# clock_sync.net
KiCad netlist of a schematic drawn in EAGLE
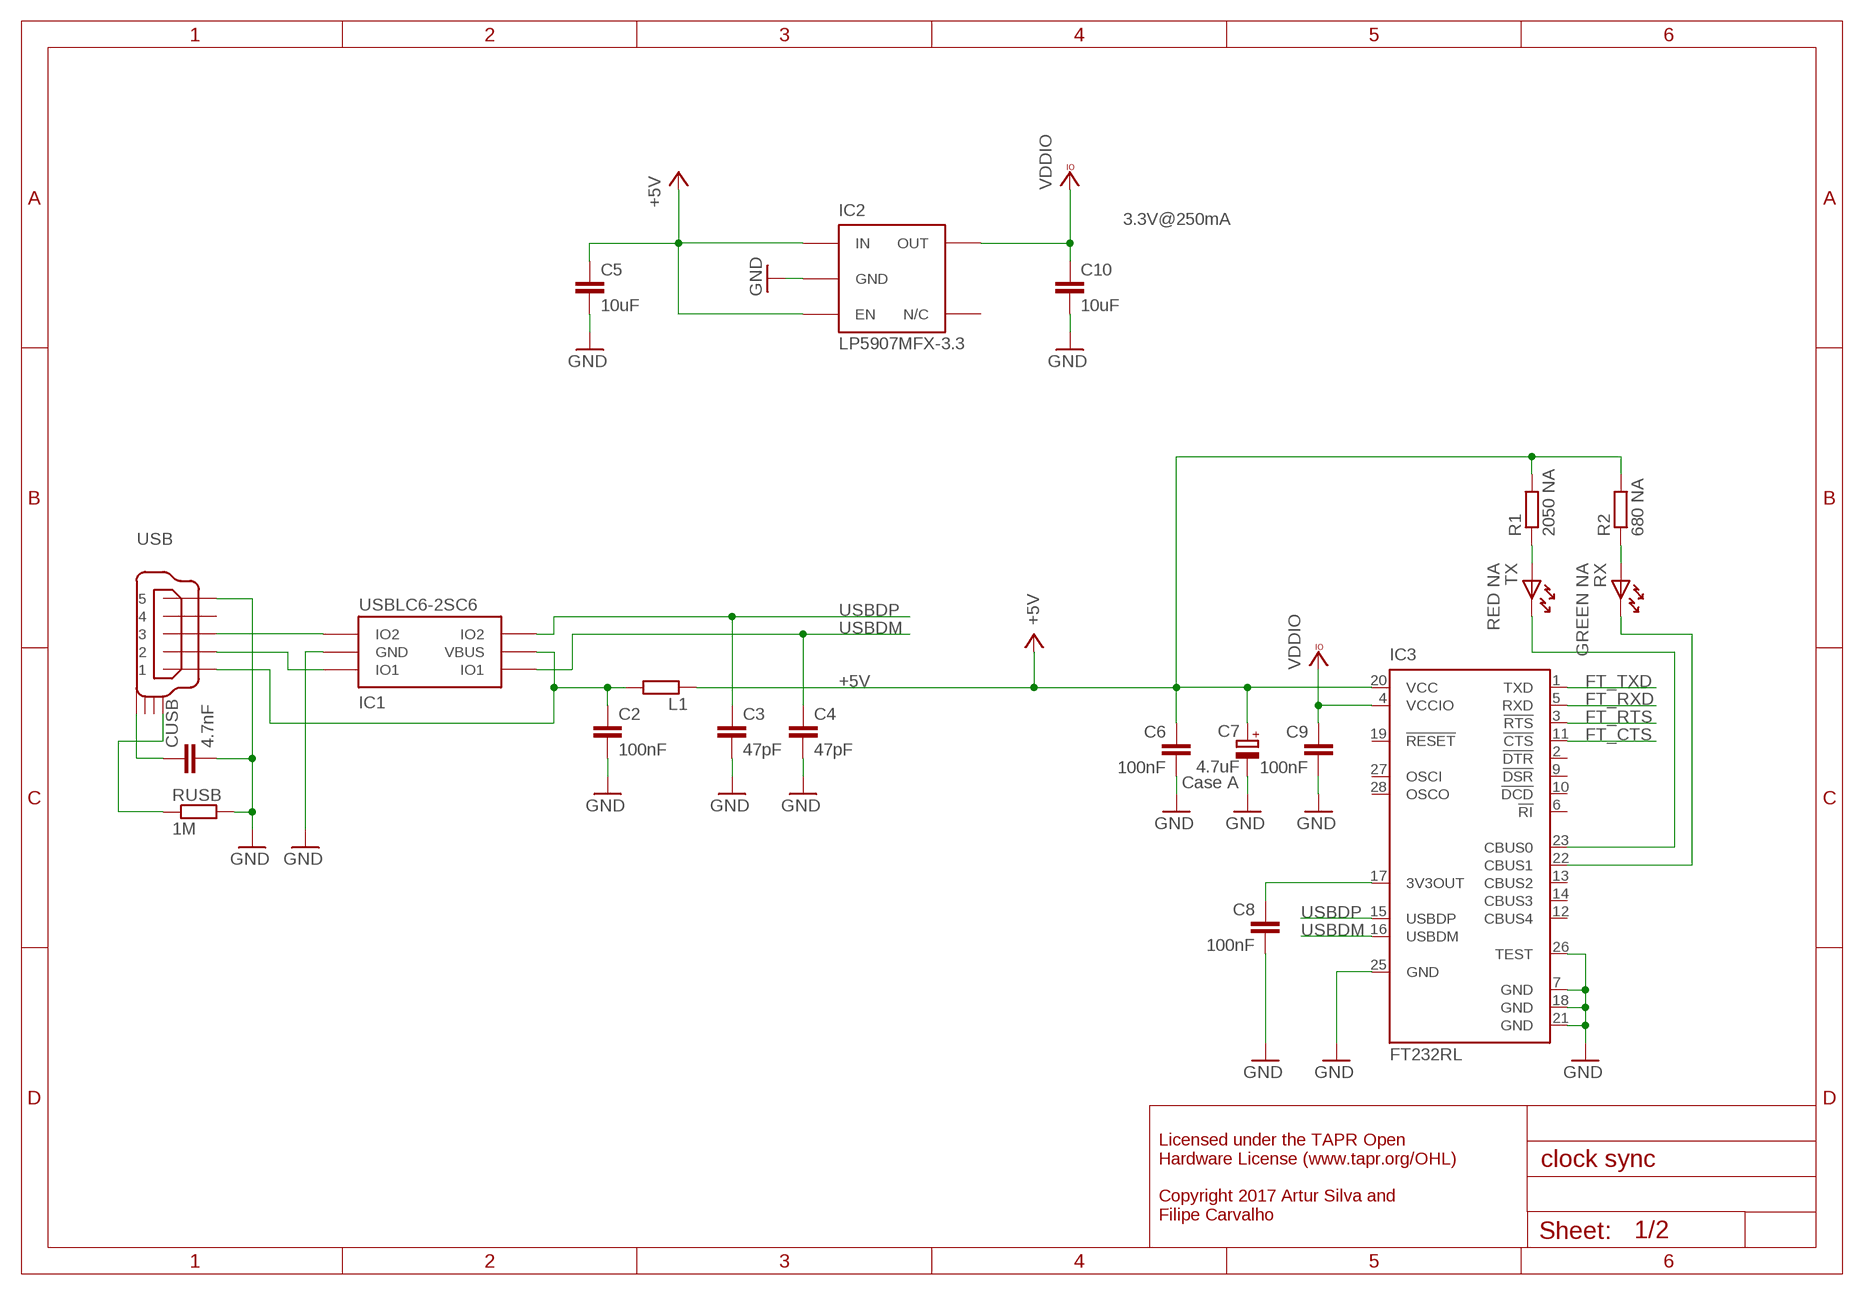
[diagram p0: schematic, sheet 1]
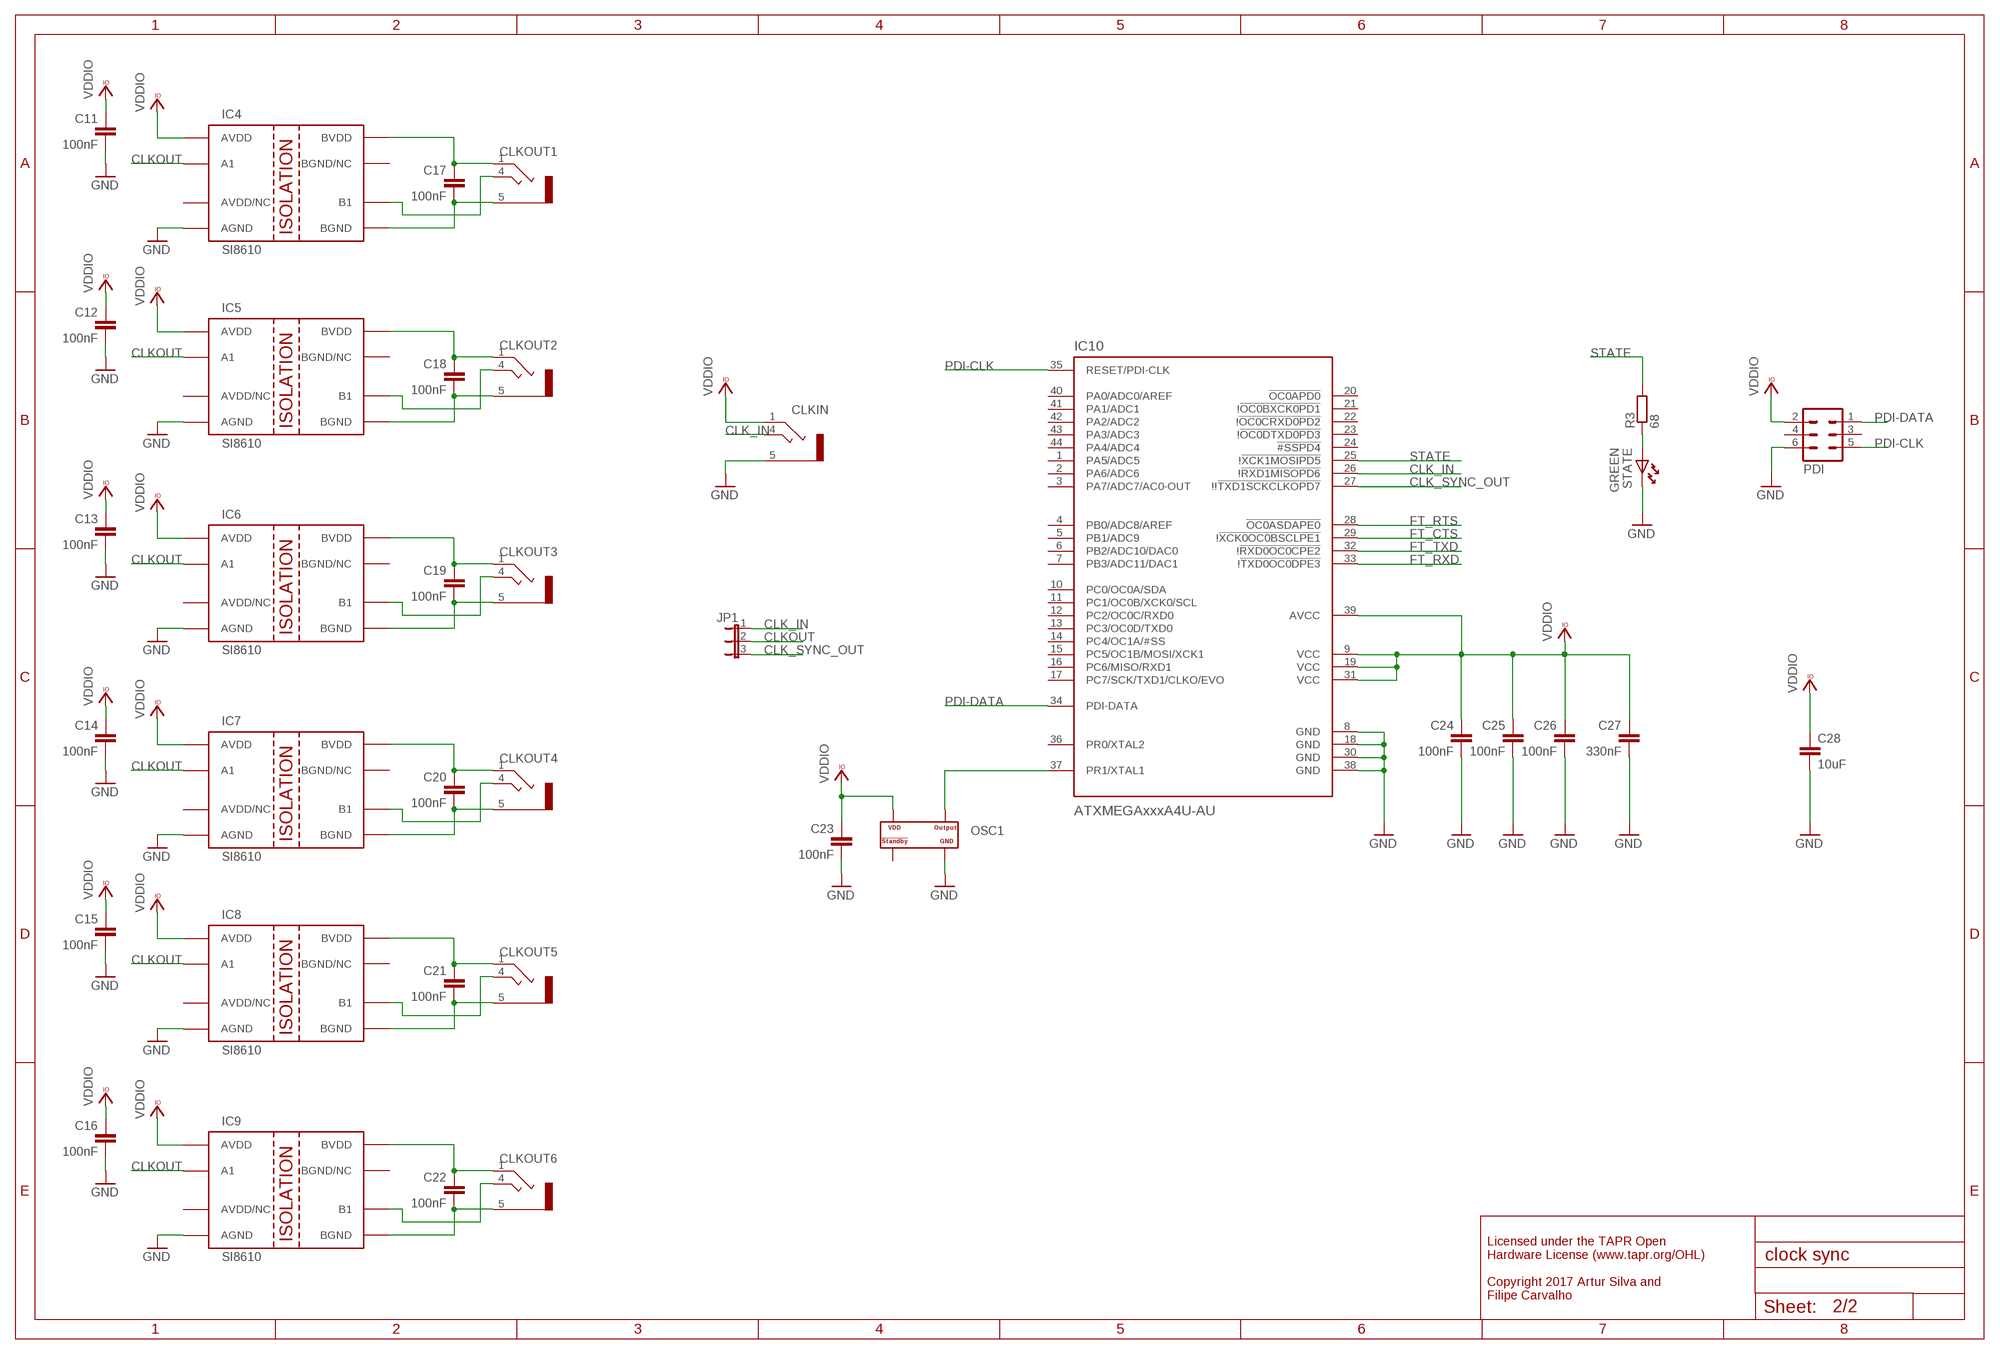
[diagram p1: schematic, sheet 2]

(export (version "E")
  (design (tool "Eeschema 10.0.6"))
  (components
    (comp (ref "C11")
      (value "100nF")
      (footprint "eagle-import:C0402")
      (libsource (lib "eagle-import") (part "C-EUC0402"))
    )
    (comp (ref "C12")
      (value "100nF")
      (footprint "eagle-import:C0402")
      (libsource (lib "eagle-import") (part "C-EUC0402"))
    )
    (comp (ref "C13")
      (value "100nF")
      (footprint "eagle-import:C0402")
      (libsource (lib "eagle-import") (part "C-EUC0402"))
    )
    (comp (ref "C14")
      (value "100nF")
      (footprint "eagle-import:C0402")
      (libsource (lib "eagle-import") (part "C-EUC0402"))
    )
    (comp (ref "C15")
      (value "100nF")
      (footprint "eagle-import:C0402")
      (libsource (lib "eagle-import") (part "C-EUC0402"))
    )
    (comp (ref "C16")
      (value "100nF")
      (footprint "eagle-import:C0402")
      (libsource (lib "eagle-import") (part "C-EUC0402"))
    )
    (comp (ref "C17")
      (value "100nF")
      (footprint "eagle-import:C0402")
      (libsource (lib "eagle-import") (part "C-EUC0402"))
    )
    (comp (ref "C18")
      (value "100nF")
      (footprint "eagle-import:C0402")
      (libsource (lib "eagle-import") (part "C-EUC0402"))
    )
    (comp (ref "C19")
      (value "100nF")
      (footprint "eagle-import:C0402")
      (libsource (lib "eagle-import") (part "C-EUC0402"))
    )
    (comp (ref "C20")
      (value "100nF")
      (footprint "eagle-import:C0402")
      (libsource (lib "eagle-import") (part "C-EUC0402"))
    )
    (comp (ref "C21")
      (value "100nF")
      (footprint "eagle-import:C0402")
      (libsource (lib "eagle-import") (part "C-EUC0402"))
    )
    (comp (ref "C22")
      (value "100nF")
      (footprint "eagle-import:C0402")
      (libsource (lib "eagle-import") (part "C-EUC0402"))
    )
    (comp (ref "C23")
      (value "100nF")
      (footprint "eagle-import:C0402")
      (libsource (lib "eagle-import") (part "C-EUC0402"))
    )
    (comp (ref "C24")
      (value "100nF")
      (footprint "eagle-import:C0402")
      (libsource (lib "eagle-import") (part "C-EUC0402"))
    )
    (comp (ref "C25")
      (value "100nF")
      (footprint "eagle-import:C0402")
      (libsource (lib "eagle-import") (part "C-EUC0402"))
    )
    (comp (ref "C26")
      (value "100nF")
      (footprint "eagle-import:C0402")
      (libsource (lib "eagle-import") (part "C-EUC0402"))
    )
    (comp (ref "C27")
      (value "330nF")
      (footprint "eagle-import:C0402")
      (libsource (lib "eagle-import") (part "C-EUC0402"))
    )
    (comp (ref "C28")
      (value "10uF")
      (footprint "eagle-import:C0603")
      (libsource (lib "eagle-import") (part "C-EUC0603"))
    )
    (comp (ref "CLKIN")
      (value "STEREO_JACK")
      (footprint "eagle-import:35RASMT2BHNTRX")
      (libsource (lib "eagle-import") (part "STEREO_JACK"))
    )
    (comp (ref "CLKOUT1")
      (value "STEREO_JACK")
      (footprint "eagle-import:35RASMT2BHNTRX")
      (libsource (lib "eagle-import") (part "STEREO_JACK"))
    )
    (comp (ref "CLKOUT2")
      (value "STEREO_JACK")
      (footprint "eagle-import:35RASMT2BHNTRX")
      (libsource (lib "eagle-import") (part "STEREO_JACK"))
    )
    (comp (ref "CLKOUT3")
      (value "STEREO_JACK")
      (footprint "eagle-import:35RASMT2BHNTRX")
      (libsource (lib "eagle-import") (part "STEREO_JACK"))
    )
    (comp (ref "CLKOUT4")
      (value "STEREO_JACK")
      (footprint "eagle-import:35RASMT2BHNTRX")
      (libsource (lib "eagle-import") (part "STEREO_JACK"))
    )
    (comp (ref "CLKOUT5")
      (value "STEREO_JACK")
      (footprint "eagle-import:35RASMT2BHNTRX")
      (libsource (lib "eagle-import") (part "STEREO_JACK"))
    )
    (comp (ref "CLKOUT6")
      (value "STEREO_JACK")
      (footprint "eagle-import:35RASMT2BHNTRX")
      (libsource (lib "eagle-import") (part "STEREO_JACK"))
    )
    (comp (ref "IC4")
      (value "SI8610")
      (footprint "eagle-import:SO-08")
      (libsource (lib "eagle-import") (part "SI8610"))
    )
    (comp (ref "IC5")
      (value "SI8610")
      (footprint "eagle-import:SO-08")
      (libsource (lib "eagle-import") (part "SI8610"))
    )
    (comp (ref "IC6")
      (value "SI8610")
      (footprint "eagle-import:SO-08")
      (libsource (lib "eagle-import") (part "SI8610"))
    )
    (comp (ref "IC7")
      (value "SI8610")
      (footprint "eagle-import:SO-08")
      (libsource (lib "eagle-import") (part "SI8610"))
    )
    (comp (ref "IC8")
      (value "SI8610")
      (footprint "eagle-import:SO-08")
      (libsource (lib "eagle-import") (part "SI8610"))
    )
    (comp (ref "IC9")
      (value "SI8610")
      (footprint "eagle-import:SO-08")
      (libsource (lib "eagle-import") (part "SI8610"))
    )
    (comp (ref "IC10")
      (value "ATXMEGAxxxA4U-AU")
      (footprint "eagle-import:QFP80P1200X1200X120-44N")
      (libsource (lib "eagle-import") (part "AT-XMEGA-XXA4-AU"))
    )
    (comp (ref "JP1")
      (value "JP2E\"")
      (footprint "eagle-import:JP2_NO_NUMBERS")
      (libsource (lib "eagle-import") (part "JP2E{dblquote}"))
    )
    (comp (ref "OSC1")
      (value "OSCILLATOR")
      (footprint "eagle-import:OSCILLATOR_3.2X2.5")
      (libsource (lib "eagle-import") (part "OSCILLATOR"))
    )
    (comp (ref "PDI")
      (value "MA03-2")
      (footprint "eagle-import:MA03-2")
      (libsource (lib "eagle-import") (part "MA03-2"))
    )
    (comp (ref "R3")
      (value "68")
      (footprint "eagle-import:R0402")
      (libsource (lib "eagle-import") (part "R-EU_R0402"))
    )
    (comp (ref "STATE")
      (value "GREEN")
      (footprint "eagle-import:LED_HAND")
      (libsource (lib "eagle-import") (part "LEDHAND"))
    )
    (comp (ref "C2")
      (value "100nF")
      (footprint "eagle-import:C0402")
      (libsource (lib "eagle-import") (part "C-EUC0402"))
    )
    (comp (ref "C3")
      (value "47pF")
      (footprint "eagle-import:C0402")
      (libsource (lib "eagle-import") (part "C-EUC0402"))
    )
    (comp (ref "C4")
      (value "47pF")
      (footprint "eagle-import:C0402")
      (libsource (lib "eagle-import") (part "C-EUC0402"))
    )
    (comp (ref "C5")
      (value "10uF")
      (footprint "eagle-import:C0603")
      (libsource (lib "eagle-import") (part "C-EUC0603"))
    )
    (comp (ref "C6")
      (value "100nF")
      (footprint "eagle-import:C0402")
      (libsource (lib "eagle-import") (part "C-EUC0402"))
    )
    (comp (ref "C7")
      (value "4.7uF")
      (footprint "eagle-import:A_3216-18W")
      (libsource (lib "eagle-import") (part "CPOL-EUA/3216-18W"))
    )
    (comp (ref "C8")
      (value "100nF")
      (footprint "eagle-import:C0402")
      (libsource (lib "eagle-import") (part "C-EUC0402"))
    )
    (comp (ref "C9")
      (value "100nF")
      (footprint "eagle-import:C0402")
      (libsource (lib "eagle-import") (part "C-EUC0402"))
    )
    (comp (ref "C10")
      (value "10uF")
      (footprint "eagle-import:C0603")
      (libsource (lib "eagle-import") (part "C-EUC0603"))
    )
    (comp (ref "CUSB")
      (value "4.7nF")
      (footprint "eagle-import:C0402")
      (libsource (lib "eagle-import") (part "C-EUC0402"))
    )
    (comp (ref "IC1")
      (value "USBLC6-2SC6")
      (footprint "eagle-import:SOT23-6L")
      (libsource (lib "eagle-import") (part "USBLC6-2"))
    )
    (comp (ref "IC2")
      (value "LP5907MFX-3.3")
      (footprint "eagle-import:TSOT23-5")
      (libsource (lib "eagle-import") (part "TLV700XX"))
    )
    (comp (ref "IC3")
      (value "FT232RL")
      (footprint "eagle-import:SSOP28")
      (libsource (lib "eagle-import") (part "FT232RL"))
    )
    (comp (ref "L1")
      (value "???")
      (footprint "eagle-import:R0805")
      (libsource (lib "eagle-import") (part "R-EU_R0805"))
    )
    (comp (ref "R1")
      (value "2050 NA")
      (footprint "eagle-import:R0402")
      (libsource (lib "eagle-import") (part "R-EU_R0402"))
    )
    (comp (ref "R2")
      (value "680 NA")
      (footprint "eagle-import:R0402")
      (libsource (lib "eagle-import") (part "R-EU_R0402"))
    )
    (comp (ref "RUSB")
      (value "1M")
      (footprint "eagle-import:R0402")
      (libsource (lib "eagle-import") (part "R-EU_R0402"))
    )
    (comp (ref "RX")
      (value "GREEN NA")
      (footprint "eagle-import:LED_HAND")
      (libsource (lib "eagle-import") (part "LEDHAND"))
    )
    (comp (ref "TX")
      (value "RED NA")
      (footprint "eagle-import:LED_HAND")
      (libsource (lib "eagle-import") (part "LEDHAND"))
    )
    (comp (ref "USB")
      (value "USB_MINI_B")
      (footprint "eagle-import:240-0002-1")
      (libsource (lib "eagle-import") (part "USB_MINI_B"))
    )
  )
  (nets
    (net (code "1") (name "+5V") (class "Default")
      (node (ref "C5") (pin "1") (pinfunction "1_1") (pintype "passive"))
      (node (ref "C6") (pin "1") (pinfunction "1_1") (pintype "passive"))
      (node (ref "C7") (pin "+") (pinfunction "+_+") (pintype "passive"))
      (node (ref "IC2") (pin "1") (pinfunction "IN_1") (pintype "bidirectional"))
      (node (ref "IC2") (pin "3") (pinfunction "EN_3") (pintype "bidirectional"))
      (node (ref "IC3") (pin "20") (pinfunction "VCC_20") (pintype "power_in"))
      (node (ref "L1") (pin "1") (pinfunction "1_1") (pintype "passive"))
      (node (ref "R1") (pin "2") (pinfunction "2_2") (pintype "passive"))
      (node (ref "R2") (pin "2") (pinfunction "2_2") (pintype "passive"))
    )
    (net (code "2") (name "CLKOUT") (class "Default")
      (node (ref "IC4") (pin "2") (pinfunction "A1_2") (pintype "bidirectional"))
      (node (ref "IC5") (pin "2") (pinfunction "A1_2") (pintype "bidirectional"))
      (node (ref "IC6") (pin "2") (pinfunction "A1_2") (pintype "bidirectional"))
      (node (ref "IC7") (pin "2") (pinfunction "A1_2") (pintype "bidirectional"))
      (node (ref "IC8") (pin "2") (pinfunction "A1_2") (pintype "bidirectional"))
      (node (ref "IC9") (pin "2") (pinfunction "A1_2") (pintype "bidirectional"))
      (node (ref "JP1") (pin "2") (pinfunction "2_2") (pintype "passive"))
    )
    (net (code "3") (name "CLK_IN") (class "Default")
      (node (ref "CLKIN") (pin "4") (pinfunction "4_4") (pintype "passive"))
      (node (ref "IC10") (pin "26") (pinfunction "~RXD1MISOPD6_26") (pintype "bidirectional"))
      (node (ref "JP1") (pin "1") (pinfunction "1_1") (pintype "passive"))
    )
    (net (code "4") (name "CLK_SYNC_OUT") (class "Default")
      (node (ref "IC10") (pin "27") (pinfunction "~~{TXD1SCKCLKOPD7}_27") (pintype "bidirectional"))
      (node (ref "JP1") (pin "3") (pinfunction "3_3") (pintype "passive"))
    )
    (net (code "5") (name "FT_CTS") (class "Default")
      (node (ref "IC10") (pin "29") (pinfunction "~XCK0OC0BSCLPE1_29") (pintype "bidirectional"))
      (node (ref "IC3") (pin "11") (pinfunction "~{CTS}_11") (pintype "input"))
    )
    (net (code "6") (name "FT_RTS") (class "Default")
      (node (ref "IC10") (pin "28") (pinfunction "~{OC0ASDAPE0}_28") (pintype "bidirectional"))
      (node (ref "IC3") (pin "3") (pinfunction "~{RTS}_3") (pintype "output"))
    )
    (net (code "7") (name "FT_RXD") (class "Default")
      (node (ref "IC10") (pin "33") (pinfunction "~TXD0OC0DPE3_33") (pintype "bidirectional"))
      (node (ref "IC3") (pin "5") (pinfunction "RXD_5") (pintype "input"))
    )
    (net (code "8") (name "FT_TXD") (class "Default")
      (node (ref "IC10") (pin "32") (pinfunction "~RXD0OC0CPE2_32") (pintype "bidirectional"))
      (node (ref "IC3") (pin "1") (pinfunction "TXD_1") (pintype "output"))
    )
    (net (code "9") (name "GND") (class "Default")
      (node (ref "C10") (pin "2") (pinfunction "2_2") (pintype "passive"))
      (node (ref "C11") (pin "2") (pinfunction "2_2") (pintype "passive"))
      (node (ref "C12") (pin "2") (pinfunction "2_2") (pintype "passive"))
      (node (ref "C13") (pin "2") (pinfunction "2_2") (pintype "passive"))
      (node (ref "C14") (pin "2") (pinfunction "2_2") (pintype "passive"))
      (node (ref "C15") (pin "2") (pinfunction "2_2") (pintype "passive"))
      (node (ref "C16") (pin "2") (pinfunction "2_2") (pintype "passive"))
      (node (ref "C2") (pin "2") (pinfunction "2_2") (pintype "passive"))
      (node (ref "C23") (pin "2") (pinfunction "2_2") (pintype "passive"))
      (node (ref "C24") (pin "2") (pinfunction "2_2") (pintype "passive"))
      (node (ref "C25") (pin "2") (pinfunction "2_2") (pintype "passive"))
      (node (ref "C26") (pin "2") (pinfunction "2_2") (pintype "passive"))
      (node (ref "C27") (pin "2") (pinfunction "2_2") (pintype "passive"))
      (node (ref "C28") (pin "2") (pinfunction "2_2") (pintype "passive"))
      (node (ref "C3") (pin "2") (pinfunction "2_2") (pintype "passive"))
      (node (ref "C4") (pin "2") (pinfunction "2_2") (pintype "passive"))
      (node (ref "C5") (pin "2") (pinfunction "2_2") (pintype "passive"))
      (node (ref "C6") (pin "2") (pinfunction "2_2") (pintype "passive"))
      (node (ref "C7") (pin "-") (pinfunction "-_-") (pintype "passive"))
      (node (ref "C8") (pin "2") (pinfunction "2_2") (pintype "passive"))
      (node (ref "C9") (pin "2") (pinfunction "2_2") (pintype "passive"))
      (node (ref "CLKIN") (pin "5") (pinfunction "5_5") (pintype "passive"))
      (node (ref "CUSB") (pin "2") (pinfunction "2_2") (pintype "passive"))
      (node (ref "IC1") (pin "P$2") (pinfunction "GND_P$2") (pintype "bidirectional"))
      (node (ref "IC10") (pin "18") (pinfunction "GND_18") (pintype "power_in"))
      (node (ref "IC10") (pin "30") (pinfunction "GND_30") (pintype "power_in"))
      (node (ref "IC10") (pin "38") (pinfunction "GND_38") (pintype "power_in"))
      (node (ref "IC10") (pin "8") (pinfunction "GND_8") (pintype "power_in"))
      (node (ref "IC2") (pin "2") (pinfunction "GND_2") (pintype "bidirectional"))
      (node (ref "IC3") (pin "18") (pinfunction "GND_18") (pintype "power_in"))
      (node (ref "IC3") (pin "21") (pinfunction "GND_21") (pintype "power_in"))
      (node (ref "IC3") (pin "25") (pinfunction "GND_25") (pintype "power_in"))
      (node (ref "IC3") (pin "26") (pinfunction "TEST_26") (pintype "input"))
      (node (ref "IC3") (pin "7") (pinfunction "GND_7") (pintype "power_in"))
      (node (ref "IC4") (pin "4") (pinfunction "AGND_4") (pintype "bidirectional"))
      (node (ref "IC5") (pin "4") (pinfunction "AGND_4") (pintype "bidirectional"))
      (node (ref "IC6") (pin "4") (pinfunction "AGND_4") (pintype "bidirectional"))
      (node (ref "IC7") (pin "4") (pinfunction "AGND_4") (pintype "bidirectional"))
      (node (ref "IC8") (pin "4") (pinfunction "AGND_4") (pintype "bidirectional"))
      (node (ref "IC9") (pin "4") (pinfunction "AGND_4") (pintype "bidirectional"))
      (node (ref "OSC1") (pin "P$2") (pinfunction "GND_P$2") (pintype "passive"))
      (node (ref "PDI") (pin "6") (pinfunction "6_6") (pintype "passive"))
      (node (ref "RUSB") (pin "2") (pinfunction "2_2") (pintype "passive"))
      (node (ref "STATE") (pin "K") (pinfunction "K_K") (pintype "bidirectional"))
      (node (ref "USB") (pin "P$5") (pinfunction "5_P$5") (pintype "bidirectional"))
    )
    (net (code "10") (name "Net-(IC1-VBUS)") (class "Default")
      (node (ref "C2") (pin "1") (pinfunction "1_1") (pintype "passive"))
      (node (ref "IC1") (pin "P$5") (pinfunction "VBUS_P$5") (pintype "bidirectional"))
      (node (ref "L1") (pin "2") (pinfunction "2_2") (pintype "passive"))
      (node (ref "USB") (pin "P$1") (pinfunction "1_P$1") (pintype "bidirectional"))
    )
    (net (code "11") (name "Net-(IC3-3V3OUT)") (class "Default")
      (node (ref "C8") (pin "1") (pinfunction "1_1") (pintype "passive"))
      (node (ref "IC3") (pin "17") (pinfunction "3V3OUT_17") (pintype "output"))
    )
    (net (code "12") (name "Net-(IC3-CBUS0)") (class "Default")
      (node (ref "IC3") (pin "23") (pinfunction "CBUS0_23") (pintype "bidirectional"))
      (node (ref "TX") (pin "K") (pinfunction "K_K") (pintype "bidirectional"))
    )
    (net (code "13") (name "Net-(IC3-CBUS1)") (class "Default")
      (node (ref "IC3") (pin "22") (pinfunction "CBUS1_22") (pintype "bidirectional"))
      (node (ref "RX") (pin "K") (pinfunction "K_K") (pintype "bidirectional"))
    )
    (net (code "14") (name "Net-(IC4-B1)") (class "Default")
      (node (ref "CLKOUT1") (pin "4") (pinfunction "4_4") (pintype "passive"))
      (node (ref "IC4") (pin "6") (pinfunction "B1_6") (pintype "bidirectional"))
    )
    (net (code "15") (name "Net-(IC4-BGND)") (class "Default")
      (node (ref "C17") (pin "2") (pinfunction "2_2") (pintype "passive"))
      (node (ref "CLKOUT1") (pin "5") (pinfunction "5_5") (pintype "passive"))
      (node (ref "IC4") (pin "5") (pinfunction "BGND_5") (pintype "bidirectional"))
    )
    (net (code "16") (name "Net-(IC4-BVDD)") (class "Default")
      (node (ref "C17") (pin "1") (pinfunction "1_1") (pintype "passive"))
      (node (ref "CLKOUT1") (pin "1") (pinfunction "1_1") (pintype "passive"))
      (node (ref "IC4") (pin "8") (pinfunction "BVDD_8") (pintype "bidirectional"))
    )
    (net (code "17") (name "Net-(IC5-B1)") (class "Default")
      (node (ref "CLKOUT2") (pin "4") (pinfunction "4_4") (pintype "passive"))
      (node (ref "IC5") (pin "6") (pinfunction "B1_6") (pintype "bidirectional"))
    )
    (net (code "18") (name "Net-(IC5-BGND)") (class "Default")
      (node (ref "C18") (pin "2") (pinfunction "2_2") (pintype "passive"))
      (node (ref "CLKOUT2") (pin "5") (pinfunction "5_5") (pintype "passive"))
      (node (ref "IC5") (pin "5") (pinfunction "BGND_5") (pintype "bidirectional"))
    )
    (net (code "19") (name "Net-(IC5-BVDD)") (class "Default")
      (node (ref "C18") (pin "1") (pinfunction "1_1") (pintype "passive"))
      (node (ref "CLKOUT2") (pin "1") (pinfunction "1_1") (pintype "passive"))
      (node (ref "IC5") (pin "8") (pinfunction "BVDD_8") (pintype "bidirectional"))
    )
    (net (code "20") (name "Net-(IC6-B1)") (class "Default")
      (node (ref "CLKOUT3") (pin "4") (pinfunction "4_4") (pintype "passive"))
      (node (ref "IC6") (pin "6") (pinfunction "B1_6") (pintype "bidirectional"))
    )
    (net (code "21") (name "Net-(IC6-BGND)") (class "Default")
      (node (ref "C19") (pin "2") (pinfunction "2_2") (pintype "passive"))
      (node (ref "CLKOUT3") (pin "5") (pinfunction "5_5") (pintype "passive"))
      (node (ref "IC6") (pin "5") (pinfunction "BGND_5") (pintype "bidirectional"))
    )
    (net (code "22") (name "Net-(IC6-BVDD)") (class "Default")
      (node (ref "C19") (pin "1") (pinfunction "1_1") (pintype "passive"))
      (node (ref "CLKOUT3") (pin "1") (pinfunction "1_1") (pintype "passive"))
      (node (ref "IC6") (pin "8") (pinfunction "BVDD_8") (pintype "bidirectional"))
    )
    (net (code "23") (name "Net-(IC7-B1)") (class "Default")
      (node (ref "CLKOUT4") (pin "4") (pinfunction "4_4") (pintype "passive"))
      (node (ref "IC7") (pin "6") (pinfunction "B1_6") (pintype "bidirectional"))
    )
    (net (code "24") (name "Net-(IC7-BGND)") (class "Default")
      (node (ref "C20") (pin "2") (pinfunction "2_2") (pintype "passive"))
      (node (ref "CLKOUT4") (pin "5") (pinfunction "5_5") (pintype "passive"))
      (node (ref "IC7") (pin "5") (pinfunction "BGND_5") (pintype "bidirectional"))
    )
    (net (code "25") (name "Net-(IC7-BVDD)") (class "Default")
      (node (ref "C20") (pin "1") (pinfunction "1_1") (pintype "passive"))
      (node (ref "CLKOUT4") (pin "1") (pinfunction "1_1") (pintype "passive"))
      (node (ref "IC7") (pin "8") (pinfunction "BVDD_8") (pintype "bidirectional"))
    )
    (net (code "26") (name "Net-(IC8-B1)") (class "Default")
      (node (ref "CLKOUT5") (pin "4") (pinfunction "4_4") (pintype "passive"))
      (node (ref "IC8") (pin "6") (pinfunction "B1_6") (pintype "bidirectional"))
    )
    (net (code "27") (name "Net-(IC8-BGND)") (class "Default")
      (node (ref "C21") (pin "2") (pinfunction "2_2") (pintype "passive"))
      (node (ref "CLKOUT5") (pin "5") (pinfunction "5_5") (pintype "passive"))
      (node (ref "IC8") (pin "5") (pinfunction "BGND_5") (pintype "bidirectional"))
    )
    (net (code "28") (name "Net-(IC8-BVDD)") (class "Default")
      (node (ref "C21") (pin "1") (pinfunction "1_1") (pintype "passive"))
      (node (ref "CLKOUT5") (pin "1") (pinfunction "1_1") (pintype "passive"))
      (node (ref "IC8") (pin "8") (pinfunction "BVDD_8") (pintype "bidirectional"))
    )
    (net (code "29") (name "Net-(IC9-B1)") (class "Default")
      (node (ref "CLKOUT6") (pin "4") (pinfunction "4_4") (pintype "passive"))
      (node (ref "IC9") (pin "6") (pinfunction "B1_6") (pintype "bidirectional"))
    )
    (net (code "30") (name "Net-(IC9-BGND)") (class "Default")
      (node (ref "C22") (pin "2") (pinfunction "2_2") (pintype "passive"))
      (node (ref "CLKOUT6") (pin "5") (pinfunction "5_5") (pintype "passive"))
      (node (ref "IC9") (pin "5") (pinfunction "BGND_5") (pintype "bidirectional"))
    )
    (net (code "31") (name "Net-(IC9-BVDD)") (class "Default")
      (node (ref "C22") (pin "1") (pinfunction "1_1") (pintype "passive"))
      (node (ref "CLKOUT6") (pin "1") (pinfunction "1_1") (pintype "passive"))
      (node (ref "IC9") (pin "8") (pinfunction "BVDD_8") (pintype "bidirectional"))
    )
    (net (code "32") (name "Net-(IC10-PR1{slash}XTAL1)") (class "Default")
      (node (ref "IC10") (pin "37") (pinfunction "PR1/XTAL1_37") (pintype "bidirectional"))
      (node (ref "OSC1") (pin "P$3") (pinfunction "OUTPUT_P$3") (pintype "passive"))
    )
    (net (code "33") (name "Net-(R1-Pad1)") (class "Default")
      (node (ref "R1") (pin "1") (pinfunction "1_1") (pintype "passive"))
      (node (ref "TX") (pin "A") (pinfunction "A_A") (pintype "bidirectional"))
    )
    (net (code "34") (name "Net-(R2-Pad1)") (class "Default")
      (node (ref "R2") (pin "1") (pinfunction "1_1") (pintype "passive"))
      (node (ref "RX") (pin "A") (pinfunction "A_A") (pintype "bidirectional"))
    )
    (net (code "35") (name "Net-(R3-Pad1)") (class "Default")
      (node (ref "R3") (pin "1") (pinfunction "1_1") (pintype "passive"))
      (node (ref "STATE") (pin "A") (pinfunction "A_A") (pintype "bidirectional"))
    )
    (net (code "36") (name "Net-(USB-2)") (class "Default")
      (node (ref "IC1") (pin "P$1") (pinfunction "IO1_P$1") (pintype "bidirectional"))
      (node (ref "USB") (pin "P$2") (pinfunction "2_P$2") (pintype "bidirectional"))
    )
    (net (code "37") (name "Net-(USB-3)") (class "Default")
      (node (ref "IC1") (pin "P$3") (pinfunction "IO2_P$3") (pintype "bidirectional"))
      (node (ref "USB") (pin "P$3") (pinfunction "3_P$3") (pintype "bidirectional"))
    )
    (net (code "38") (name "Net-(USB-P$1)") (class "Default")
      (node (ref "RUSB") (pin "1") (pinfunction "1_1") (pintype "passive"))
      (node (ref "USB") (pin "SHIELD_1") (pinfunction "P$1_SHIELD_1") (pintype "bidirectional"))
    )
    (net (code "39") (name "Net-(USB-P$4)") (class "Default")
      (node (ref "CUSB") (pin "1") (pinfunction "1_1") (pintype "passive"))
      (node (ref "USB") (pin "SHIELD_4") (pinfunction "P$4_SHIELD_4") (pintype "bidirectional"))
    )
    (net (code "40") (name "PDI-CLK") (class "Default")
      (node (ref "IC10") (pin "35") (pinfunction "RESET/PDI-CLK_35") (pintype "input"))
      (node (ref "PDI") (pin "5") (pinfunction "5_5") (pintype "passive"))
    )
    (net (code "41") (name "PDI-DATA") (class "Default")
      (node (ref "IC10") (pin "34") (pinfunction "PDI-DATA_34") (pintype "bidirectional"))
      (node (ref "PDI") (pin "1") (pinfunction "1_1") (pintype "passive"))
    )
    (net (code "42") (name "STATE") (class "Default")
      (node (ref "IC10") (pin "25") (pinfunction "~XCK1MOSIPD5_25") (pintype "bidirectional"))
      (node (ref "R3") (pin "2") (pinfunction "2_2") (pintype "passive"))
    )
    (net (code "43") (name "USBDM") (class "Default")
      (node (ref "C4") (pin "1") (pinfunction "1_1") (pintype "passive"))
      (node (ref "IC1") (pin "P$6") (pinfunction "IO1_P$6") (pintype "bidirectional"))
      (node (ref "IC3") (pin "16") (pinfunction "USBDM_16") (pintype "bidirectional"))
    )
    (net (code "44") (name "USBDP") (class "Default")
      (node (ref "C3") (pin "1") (pinfunction "1_1") (pintype "passive"))
      (node (ref "IC1") (pin "P$4") (pinfunction "IO2_P$4") (pintype "bidirectional"))
      (node (ref "IC3") (pin "15") (pinfunction "USBDP_15") (pintype "bidirectional"))
    )
    (net (code "45") (name "VCCIO") (class "Default")
      (node (ref "C10") (pin "1") (pinfunction "1_1") (pintype "passive"))
      (node (ref "C11") (pin "1") (pinfunction "1_1") (pintype "passive"))
      (node (ref "C12") (pin "1") (pinfunction "1_1") (pintype "passive"))
      (node (ref "C13") (pin "1") (pinfunction "1_1") (pintype "passive"))
      (node (ref "C14") (pin "1") (pinfunction "1_1") (pintype "passive"))
      (node (ref "C15") (pin "1") (pinfunction "1_1") (pintype "passive"))
      (node (ref "C16") (pin "1") (pinfunction "1_1") (pintype "passive"))
      (node (ref "C23") (pin "1") (pinfunction "1_1") (pintype "passive"))
      (node (ref "C24") (pin "1") (pinfunction "1_1") (pintype "passive"))
      (node (ref "C25") (pin "1") (pinfunction "1_1") (pintype "passive"))
      (node (ref "C26") (pin "1") (pinfunction "1_1") (pintype "passive"))
      (node (ref "C27") (pin "1") (pinfunction "1_1") (pintype "passive"))
      (node (ref "C28") (pin "1") (pinfunction "1_1") (pintype "passive"))
      (node (ref "C9") (pin "1") (pinfunction "1_1") (pintype "passive"))
      (node (ref "CLKIN") (pin "1") (pinfunction "1_1") (pintype "passive"))
      (node (ref "IC10") (pin "19") (pinfunction "VCC_19") (pintype "power_in"))
      (node (ref "IC10") (pin "31") (pinfunction "VCC_31") (pintype "power_in"))
      (node (ref "IC10") (pin "39") (pinfunction "AVCC_39") (pintype "power_in"))
      (node (ref "IC10") (pin "9") (pinfunction "VCC_9") (pintype "power_in"))
      (node (ref "IC2") (pin "5") (pinfunction "OUT_5") (pintype "bidirectional"))
      (node (ref "IC3") (pin "4") (pinfunction "VCCIO_4") (pintype "power_in"))
      (node (ref "IC4") (pin "1") (pinfunction "AVDD_1") (pintype "bidirectional"))
      (node (ref "IC5") (pin "1") (pinfunction "AVDD_1") (pintype "bidirectional"))
      (node (ref "IC6") (pin "1") (pinfunction "AVDD_1") (pintype "bidirectional"))
      (node (ref "IC7") (pin "1") (pinfunction "AVDD_1") (pintype "bidirectional"))
      (node (ref "IC8") (pin "1") (pinfunction "AVDD_1") (pintype "bidirectional"))
      (node (ref "IC9") (pin "1") (pinfunction "AVDD_1") (pintype "bidirectional"))
      (node (ref "OSC1") (pin "P$4") (pinfunction "VDD_P$4") (pintype "passive"))
      (node (ref "PDI") (pin "2") (pinfunction "2_2") (pintype "passive"))
    )
    (net (code "46") (name "unconnected-(IC2-N{slash}C-Pad4)") (class "Default")
      (node (ref "IC2") (pin "4") (pinfunction "N/C_4") (pintype "bidirectional"))
    )
    (net (code "47") (name "unconnected-(IC3-CBUS2-Pad13)") (class "Default")
      (node (ref "IC3") (pin "13") (pinfunction "CBUS2_13") (pintype "bidirectional"))
    )
    (net (code "48") (name "unconnected-(IC3-CBUS3-Pad14)") (class "Default")
      (node (ref "IC3") (pin "14") (pinfunction "CBUS3_14") (pintype "bidirectional"))
    )
    (net (code "49") (name "unconnected-(IC3-CBUS4-Pad12)") (class "Default")
      (node (ref "IC3") (pin "12") (pinfunction "CBUS4_12") (pintype "bidirectional"))
    )
    (net (code "50") (name "unconnected-(IC3-OSCI-Pad27)") (class "Default")
      (node (ref "IC3") (pin "27") (pinfunction "OSCI_27") (pintype "input"))
    )
    (net (code "51") (name "unconnected-(IC3-OSCO-Pad28)") (class "Default")
      (node (ref "IC3") (pin "28") (pinfunction "OSCO_28") (pintype "output"))
    )
    (net (code "52") (name "unconnected-(IC3-~{DCD}-Pad10)") (class "Default")
      (node (ref "IC3") (pin "10") (pinfunction "~{DCD}_10") (pintype "input"))
    )
    (net (code "53") (name "unconnected-(IC3-~{DSR}-Pad9)") (class "Default")
      (node (ref "IC3") (pin "9") (pinfunction "~{DSR}_9") (pintype "input"))
    )
    (net (code "54") (name "unconnected-(IC3-~{DTR}-Pad2)") (class "Default")
      (node (ref "IC3") (pin "2") (pinfunction "~{DTR}_2") (pintype "output"))
    )
    (net (code "55") (name "unconnected-(IC3-~{RESET}-Pad19)") (class "Default")
      (node (ref "IC3") (pin "19") (pinfunction "~{RESET}_19") (pintype "input"))
    )
    (net (code "56") (name "unconnected-(IC3-~{RI}-Pad6)") (class "Default")
      (node (ref "IC3") (pin "6") (pinfunction "~{RI}_6") (pintype "input"))
    )
    (net (code "57") (name "unconnected-(IC4-AVDD{slash}NC-Pad3)") (class "Default")
      (node (ref "IC4") (pin "3") (pinfunction "AVDD/NC_3") (pintype "bidirectional"))
    )
    (net (code "58") (name "unconnected-(IC4-BGND{slash}NC-Pad7)") (class "Default")
      (node (ref "IC4") (pin "7") (pinfunction "BGND/NC_7") (pintype "bidirectional"))
    )
    (net (code "59") (name "unconnected-(IC5-AVDD{slash}NC-Pad3)") (class "Default")
      (node (ref "IC5") (pin "3") (pinfunction "AVDD/NC_3") (pintype "bidirectional"))
    )
    (net (code "60") (name "unconnected-(IC5-BGND{slash}NC-Pad7)") (class "Default")
      (node (ref "IC5") (pin "7") (pinfunction "BGND/NC_7") (pintype "bidirectional"))
    )
    (net (code "61") (name "unconnected-(IC6-AVDD{slash}NC-Pad3)") (class "Default")
      (node (ref "IC6") (pin "3") (pinfunction "AVDD/NC_3") (pintype "bidirectional"))
    )
    (net (code "62") (name "unconnected-(IC6-BGND{slash}NC-Pad7)") (class "Default")
      (node (ref "IC6") (pin "7") (pinfunction "BGND/NC_7") (pintype "bidirectional"))
    )
    (net (code "63") (name "unconnected-(IC7-AVDD{slash}NC-Pad3)") (class "Default")
      (node (ref "IC7") (pin "3") (pinfunction "AVDD/NC_3") (pintype "bidirectional"))
    )
    (net (code "64") (name "unconnected-(IC7-BGND{slash}NC-Pad7)") (class "Default")
      (node (ref "IC7") (pin "7") (pinfunction "BGND/NC_7") (pintype "bidirectional"))
    )
    (net (code "65") (name "unconnected-(IC8-AVDD{slash}NC-Pad3)") (class "Default")
      (node (ref "IC8") (pin "3") (pinfunction "AVDD/NC_3") (pintype "bidirectional"))
    )
    (net (code "66") (name "unconnected-(IC8-BGND{slash}NC-Pad7)") (class "Default")
      (node (ref "IC8") (pin "7") (pinfunction "BGND/NC_7") (pintype "bidirectional"))
    )
    (net (code "67") (name "unconnected-(IC9-AVDD{slash}NC-Pad3)") (class "Default")
      (node (ref "IC9") (pin "3") (pinfunction "AVDD/NC_3") (pintype "bidirectional"))
    )
    (net (code "68") (name "unconnected-(IC9-BGND{slash}NC-Pad7)") (class "Default")
      (node (ref "IC9") (pin "7") (pinfunction "BGND/NC_7") (pintype "bidirectional"))
    )
    (net (code "69") (name "unconnected-(IC10-PA0{slash}ADC0{slash}AREF-Pad40)") (class "Default")
      (node (ref "IC10") (pin "40") (pinfunction "PA0/ADC0/AREF_40") (pintype "bidirectional"))
    )
    (net (code "70") (name "unconnected-(IC10-PA1{slash}ADC1-Pad41)") (class "Default")
      (node (ref "IC10") (pin "41") (pinfunction "PA1/ADC1_41") (pintype "bidirectional"))
    )
    (net (code "71") (name "unconnected-(IC10-PA2{slash}ADC2-Pad42)") (class "Default")
      (node (ref "IC10") (pin "42") (pinfunction "PA2/ADC2_42") (pintype "bidirectional"))
    )
    (net (code "72") (name "unconnected-(IC10-PA3{slash}ADC3-Pad43)") (class "Default")
      (node (ref "IC10") (pin "43") (pinfunction "PA3/ADC3_43") (pintype "bidirectional"))
    )
    (net (code "73") (name "unconnected-(IC10-PA4{slash}ADC4-Pad44)") (class "Default")
      (node (ref "IC10") (pin "44") (pinfunction "PA4/ADC4_44") (pintype "bidirectional"))
    )
    (net (code "74") (name "unconnected-(IC10-PA5{slash}ADC5-Pad1)") (class "Default")
      (node (ref "IC10") (pin "1") (pinfunction "PA5/ADC5_1") (pintype "bidirectional"))
    )
    (net (code "75") (name "unconnected-(IC10-PA6{slash}ADC6-Pad2)") (class "Default")
      (node (ref "IC10") (pin "2") (pinfunction "PA6/ADC6_2") (pintype "bidirectional"))
    )
    (net (code "76") (name "unconnected-(IC10-PA7{slash}ADC7{slash}AC0-OUT-Pad3)") (class "Default")
      (node (ref "IC10") (pin "3") (pinfunction "PA7/ADC7/AC0-OUT_3") (pintype "bidirectional"))
    )
    (net (code "77") (name "unconnected-(IC10-PB0{slash}ADC8{slash}AREF-Pad4)") (class "Default")
      (node (ref "IC10") (pin "4") (pinfunction "PB0/ADC8/AREF_4") (pintype "bidirectional"))
    )
    (net (code "78") (name "unconnected-(IC10-PB1{slash}ADC9-Pad5)") (class "Default")
      (node (ref "IC10") (pin "5") (pinfunction "PB1/ADC9_5") (pintype "bidirectional"))
    )
    (net (code "79") (name "unconnected-(IC10-PB2{slash}ADC10{slash}DAC0-Pad6)") (class "Default")
      (node (ref "IC10") (pin "6") (pinfunction "PB2/ADC10/DAC0_6") (pintype "bidirectional"))
    )
    (net (code "80") (name "unconnected-(IC10-PB3{slash}ADC11{slash}DAC1-Pad7)") (class "Default")
      (node (ref "IC10") (pin "7") (pinfunction "PB3/ADC11/DAC1_7") (pintype "bidirectional"))
    )
    (net (code "81") (name "unconnected-(IC10-PC0{slash}OC0A{slash}SDA-Pad10)") (class "Default")
      (node (ref "IC10") (pin "10") (pinfunction "PC0/OC0A/SDA_10") (pintype "bidirectional"))
    )
    (net (code "82") (name "unconnected-(IC10-PC1{slash}OC0B{slash}XCK0{slash}SCL-Pad11)") (class "Default")
      (node (ref "IC10") (pin "11") (pinfunction "PC1/OC0B/XCK0/SCL_11") (pintype "bidirectional"))
    )
    (net (code "83") (name "unconnected-(IC10-PC2{slash}OC0C{slash}RXD0-Pad12)") (class "Default")
      (node (ref "IC10") (pin "12") (pinfunction "PC2/OC0C/RXD0_12") (pintype "bidirectional"))
    )
    (net (code "84") (name "unconnected-(IC10-PC3{slash}OC0D{slash}TXD0-Pad13)") (class "Default")
      (node (ref "IC10") (pin "13") (pinfunction "PC3/OC0D/TXD0_13") (pintype "bidirectional"))
    )
    (net (code "85") (name "unconnected-(IC10-PC4{slash}OC1A{slash}#SS-Pad14)") (class "Default")
      (node (ref "IC10") (pin "14") (pinfunction "PC4/OC1A/#SS_14") (pintype "bidirectional"))
    )
    (net (code "86") (name "unconnected-(IC10-PC5{slash}OC1B{slash}MOSI{slash}XCK1-Pad15)") (class "Default")
      (node (ref "IC10") (pin "15") (pinfunction "PC5/OC1B/MOSI/XCK1_15") (pintype "bidirectional"))
    )
    (net (code "87") (name "unconnected-(IC10-PC6{slash}MISO{slash}RXD1-Pad16)") (class "Default")
      (node (ref "IC10") (pin "16") (pinfunction "PC6/MISO/RXD1_16") (pintype "bidirectional"))
    )
    (net (code "88") (name "unconnected-(IC10-PC7{slash}SCK{slash}TXD1{slash}CLKO{slash}EVO-Pad17)") (class "Default")
      (node (ref "IC10") (pin "17") (pinfunction "PC7/SCK/TXD1/CLKO/EVO_17") (pintype "bidirectional"))
    )
    (net (code "89") (name "unconnected-(IC10-PR0{slash}XTAL2-Pad36)") (class "Default")
      (node (ref "IC10") (pin "36") (pinfunction "PR0/XTAL2_36") (pintype "bidirectional"))
    )
    (net (code "90") (name "unconnected-(IC10-~OC0BXCK0PD1-Pad21)") (class "Default")
      (node (ref "IC10") (pin "21") (pinfunction "~OC0BXCK0PD1_21") (pintype "bidirectional"))
    )
    (net (code "91") (name "unconnected-(IC10-~OC0CRXD0PD2-Pad22)") (class "Default")
      (node (ref "IC10") (pin "22") (pinfunction "~OC0CRXD0PD2_22") (pintype "bidirectional"))
    )
    (net (code "92") (name "unconnected-(IC10-~OC0DTXD0PD3-Pad23)") (class "Default")
      (node (ref "IC10") (pin "23") (pinfunction "~OC0DTXD0PD3_23") (pintype "bidirectional"))
    )
    (net (code "93") (name "unconnected-(IC10-~{#SSPD4}-Pad24)") (class "Default")
      (node (ref "IC10") (pin "24") (pinfunction "~{#SSPD4}_24") (pintype "bidirectional"))
    )
    (net (code "94") (name "unconnected-(IC10-~{OC0APD0}-Pad20)") (class "Default")
      (node (ref "IC10") (pin "20") (pinfunction "~{OC0APD0}_20") (pintype "bidirectional"))
    )
    (net (code "95") (name "unconnected-(OSC1-STANDBY#-PadP$1)") (class "Default")
      (node (ref "OSC1") (pin "P$1") (pinfunction "STANDBY#_P$1") (pintype "passive"))
    )
    (net (code "96") (name "unconnected-(PDI-Pad3)") (class "Default")
      (node (ref "PDI") (pin "3") (pinfunction "3_3") (pintype "passive"))
    )
    (net (code "97") (name "unconnected-(PDI-Pad4)") (class "Default")
      (node (ref "PDI") (pin "4") (pinfunction "4_4") (pintype "passive"))
    )
    (net (code "98") (name "unconnected-(USB-4-PadP$4)") (class "Default")
      (node (ref "USB") (pin "P$4") (pinfunction "4_P$4") (pintype "bidirectional"))
    )
    (net (code "99") (name "unconnected-(USB-P$2-PadSHIELD_2)") (class "Default")
      (node (ref "USB") (pin "SHIELD_2") (pinfunction "P$2_SHIELD_2") (pintype "bidirectional"))
    )
    (net (code "100") (name "unconnected-(USB-P$3-PadSHIELD_3)") (class "Default")
      (node (ref "USB") (pin "SHIELD_3") (pinfunction "P$3_SHIELD_3") (pintype "bidirectional"))
    )
  )
)
